# Displays.net
KiCad netlist of a schematic drawn in Altium Designer
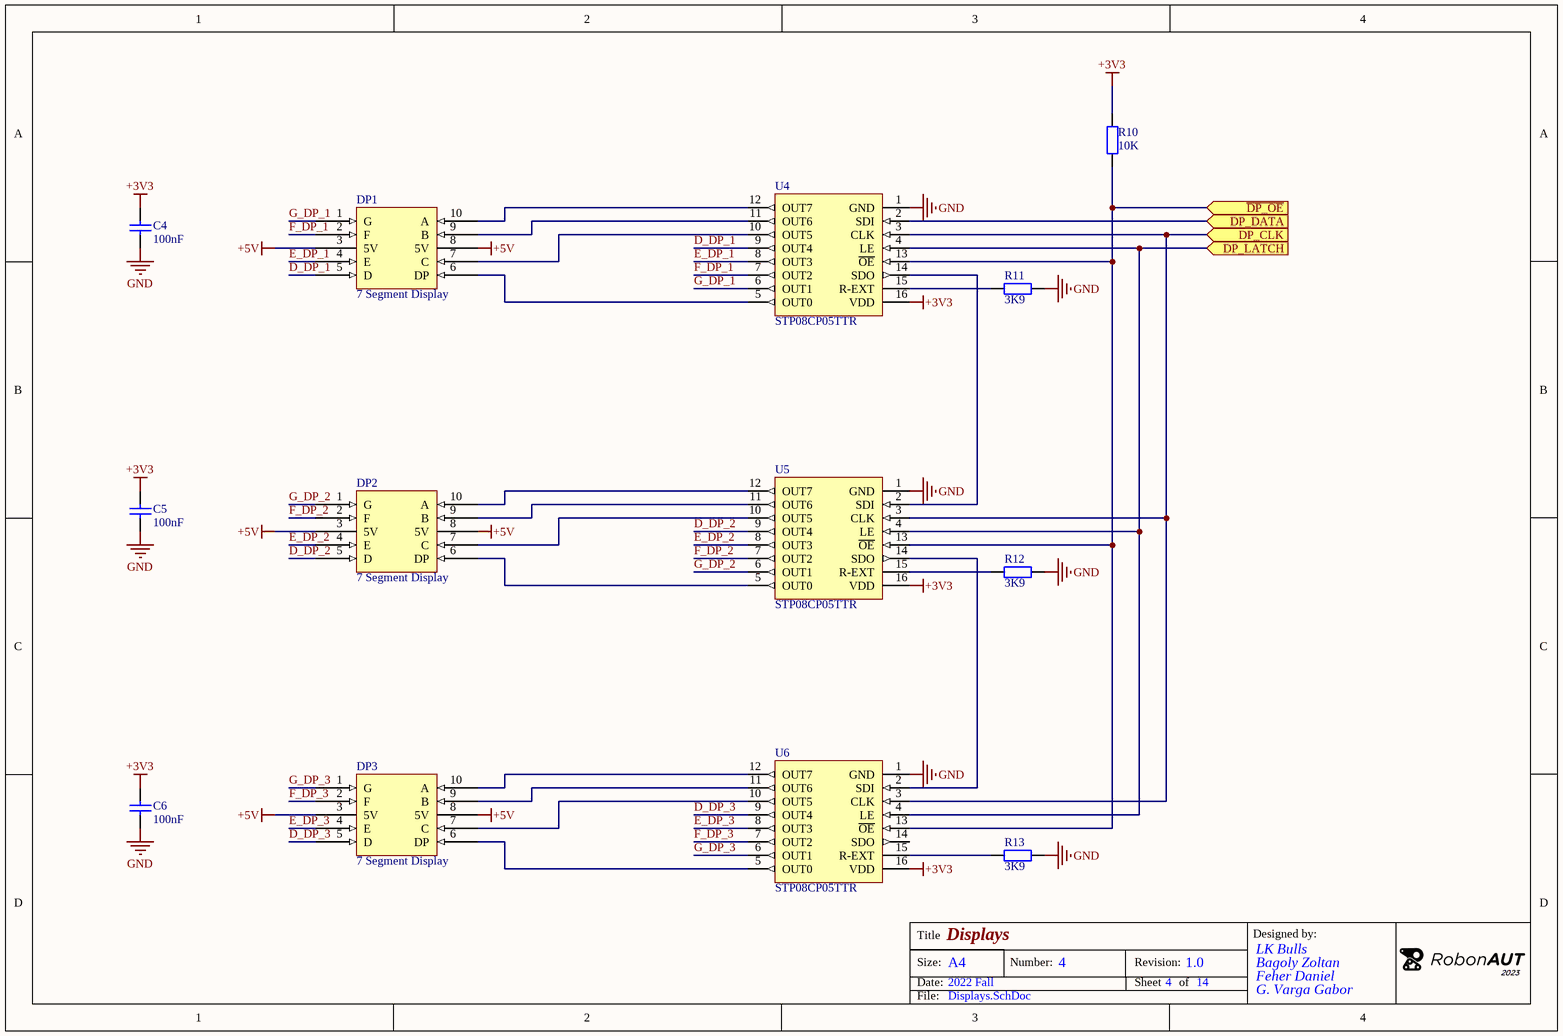
[diagram p0: Displays.SchDoc]

(export (version "E")
  (design (tool "Eeschema 10.0.6"))
  (components
    (comp (ref "C4")
      (value "100nF")
      (footprint "FP_0805_CAP_085")
      (description "Capacitor")
      (fields (field (name "TOLERANCE") "10%") (field (name "VOLTAGE") "50V"))
      (libsource (lib "LKBulls2023") (part "CAP"))
    )
    (comp (ref "C5")
      (value "100nF")
      (footprint "FP_0805_CAP_085")
      (description "Capacitor")
      (fields (field (name "TOLERANCE") "10%") (field (name "VOLTAGE") "50V"))
      (libsource (lib "LKBulls2023") (part "CAP"))
    )
    (comp (ref "C6")
      (value "100nF")
      (footprint "FP_0805_CAP_085")
      (description "Capacitor")
      (fields (field (name "TOLERANCE") "10%") (field (name "VOLTAGE") "50V"))
      (libsource (lib "LKBulls2023") (part "CAP"))
    )
    (comp (ref "DP1")
      (value "7 Segment Display")
      (footprint "FP_7_Segment_Display")
      (libsource (lib "LKBulls2023") (part "7_Segment_Display"))
    )
    (comp (ref "DP2")
      (value "7 Segment Display")
      (footprint "FP_7_Segment_Display")
      (libsource (lib "LKBulls2023") (part "7_Segment_Display"))
    )
    (comp (ref "DP3")
      (value "7 Segment Display")
      (footprint "FP_7_Segment_Display")
      (libsource (lib "LKBulls2023") (part "7_Segment_Display"))
    )
    (comp (ref "R10")
      (value "10K")
      (footprint "FP_0805_RES")
      (description "Resistor")
      (fields (field (name "TOLERANCE") "5%") (field (name "POWER") "0.125W"))
      (libsource (lib "") (part "RES_1"))
    )
    (comp (ref "R11")
      (value "3K9")
      (footprint "FP_0805_RES")
      (description "Resistor")
      (fields (field (name "TOLERANCE") "5%") (field (name "POWER") "0.125W"))
      (libsource (lib "LKBulls2023") (part "RES"))
    )
    (comp (ref "R12")
      (value "3K9")
      (footprint "FP_0805_RES")
      (description "Resistor")
      (fields (field (name "TOLERANCE") "5%") (field (name "POWER") "0.125W"))
      (libsource (lib "LKBulls2023") (part "RES"))
    )
    (comp (ref "R13")
      (value "3K9")
      (footprint "FP_0805_RES")
      (description "Resistor")
      (fields (field (name "TOLERANCE") "5%") (field (name "POWER") "0.125W"))
      (libsource (lib "LKBulls2023") (part "RES"))
    )
    (comp (ref "U4")
      (value "STP08CP05TTR")
      (footprint "SOP127P600-sajat_0095-015")
      (description "Low voltage, low current power 8-bit shift register")
      (libsource (lib "LKBulls2023") (part "STP08CP05TTR"))
    )
    (comp (ref "U5")
      (value "STP08CP05TTR")
      (footprint "SOP127P600-sajat_0095-015")
      (description "Low voltage, low current power 8-bit shift register")
      (libsource (lib "LKBulls2023") (part "STP08CP05TTR"))
    )
    (comp (ref "U6")
      (value "STP08CP05TTR")
      (footprint "SOP127P600-sajat_0095-015")
      (description "Low voltage, low current power 8-bit shift register")
      (libsource (lib "LKBulls2023") (part "STP08CP05TTR"))
    )
  )
  (nets
    (net (code "1") (name "+3V3") (class "Default")
      (node (ref "C4") (pin "2") (pinfunction "2_2") (pintype "passive"))
      (node (ref "C5") (pin "2") (pinfunction "2_2") (pintype "passive"))
      (node (ref "C6") (pin "2") (pinfunction "2_2") (pintype "passive"))
      (node (ref "R10") (pin "2") (pinfunction "2_2") (pintype "passive"))
      (node (ref "U4") (pin "16") (pinfunction "VDD_16") (pintype "power_in"))
      (node (ref "U5") (pin "16") (pinfunction "VDD_16") (pintype "power_in"))
      (node (ref "U6") (pin "16") (pinfunction "VDD_16") (pintype "power_in"))
    )
    (net (code "2") (name "+5V") (class "Default")
      (node (ref "DP1") (pin "3") (pinfunction "5V_3") (pintype "power_in"))
      (node (ref "DP1") (pin "8") (pinfunction "5V_8") (pintype "power_in"))
      (node (ref "DP2") (pin "3") (pinfunction "5V_3") (pintype "power_in"))
      (node (ref "DP2") (pin "8") (pinfunction "5V_8") (pintype "power_in"))
      (node (ref "DP3") (pin "3") (pinfunction "5V_3") (pintype "power_in"))
      (node (ref "DP3") (pin "8") (pinfunction "5V_8") (pintype "power_in"))
    )
    (net (code "3") (name "/DP_CLK") (class "Default")
      (node (ref "U4") (pin "3") (pinfunction "CLK_3") (pintype "input"))
      (node (ref "U5") (pin "3") (pinfunction "CLK_3") (pintype "input"))
      (node (ref "U6") (pin "3") (pinfunction "CLK_3") (pintype "input"))
    )
    (net (code "4") (name "/DP_DATA") (class "Default")
      (node (ref "U4") (pin "2") (pinfunction "SDI_2") (pintype "input"))
    )
    (net (code "5") (name "/DP_LATCH") (class "Default")
      (node (ref "U4") (pin "4") (pinfunction "LE_4") (pintype "input"))
      (node (ref "U5") (pin "4") (pinfunction "LE_4") (pintype "input"))
      (node (ref "U6") (pin "4") (pinfunction "LE_4") (pintype "input"))
    )
    (net (code "6") (name "/D_DP_1") (class "Default")
      (node (ref "DP1") (pin "5") (pinfunction "D_5") (pintype "input"))
      (node (ref "U4") (pin "9") (pinfunction "OUT4_9") (pintype "output"))
    )
    (net (code "7") (name "/D_DP_2") (class "Default")
      (node (ref "DP2") (pin "5") (pinfunction "D_5") (pintype "input"))
      (node (ref "U5") (pin "9") (pinfunction "OUT4_9") (pintype "output"))
    )
    (net (code "8") (name "/D_DP_3") (class "Default")
      (node (ref "DP3") (pin "5") (pinfunction "D_5") (pintype "input"))
      (node (ref "U6") (pin "9") (pinfunction "OUT4_9") (pintype "output"))
    )
    (net (code "9") (name "/E_DP_1") (class "Default")
      (node (ref "DP1") (pin "4") (pinfunction "E_4") (pintype "input"))
      (node (ref "U4") (pin "8") (pinfunction "OUT3_8") (pintype "output"))
    )
    (net (code "10") (name "/E_DP_2") (class "Default")
      (node (ref "DP2") (pin "4") (pinfunction "E_4") (pintype "input"))
      (node (ref "U5") (pin "8") (pinfunction "OUT3_8") (pintype "output"))
    )
    (net (code "11") (name "/E_DP_3") (class "Default")
      (node (ref "DP3") (pin "4") (pinfunction "E_4") (pintype "input"))
      (node (ref "U6") (pin "8") (pinfunction "OUT3_8") (pintype "output"))
    )
    (net (code "12") (name "/F_DP_1") (class "Default")
      (node (ref "DP1") (pin "2") (pinfunction "F_2") (pintype "input"))
      (node (ref "U4") (pin "7") (pinfunction "OUT2_7") (pintype "output"))
    )
    (net (code "13") (name "/F_DP_2") (class "Default")
      (node (ref "DP2") (pin "2") (pinfunction "F_2") (pintype "input"))
      (node (ref "U5") (pin "7") (pinfunction "OUT2_7") (pintype "output"))
    )
    (net (code "14") (name "/F_DP_3") (class "Default")
      (node (ref "DP3") (pin "2") (pinfunction "F_2") (pintype "input"))
      (node (ref "U6") (pin "7") (pinfunction "OUT2_7") (pintype "output"))
    )
    (net (code "15") (name "/G_DP_1") (class "Default")
      (node (ref "DP1") (pin "1") (pinfunction "G_1") (pintype "input"))
      (node (ref "U4") (pin "6") (pinfunction "OUT1_6") (pintype "output"))
    )
    (net (code "16") (name "/G_DP_2") (class "Default")
      (node (ref "DP2") (pin "1") (pinfunction "G_1") (pintype "input"))
      (node (ref "U5") (pin "6") (pinfunction "OUT1_6") (pintype "output"))
    )
    (net (code "17") (name "/G_DP_3") (class "Default")
      (node (ref "DP3") (pin "1") (pinfunction "G_1") (pintype "input"))
      (node (ref "U6") (pin "6") (pinfunction "OUT1_6") (pintype "output"))
    )
    (net (code "18") (name "/~{DP_OE}") (class "Default")
      (node (ref "R10") (pin "1") (pinfunction "1_1") (pintype "passive"))
      (node (ref "U4") (pin "13") (pinfunction "~{OE}_13") (pintype "input"))
      (node (ref "U5") (pin "13") (pinfunction "~{OE}_13") (pintype "input"))
      (node (ref "U6") (pin "13") (pinfunction "~{OE}_13") (pintype "input"))
    )
    (net (code "19") (name "GND") (class "Default")
      (node (ref "C4") (pin "1") (pinfunction "1_1") (pintype "passive"))
      (node (ref "C5") (pin "1") (pinfunction "1_1") (pintype "passive"))
      (node (ref "C6") (pin "1") (pinfunction "1_1") (pintype "passive"))
      (node (ref "R11") (pin "2") (pinfunction "2_2") (pintype "passive"))
      (node (ref "R12") (pin "2") (pinfunction "2_2") (pintype "passive"))
      (node (ref "R13") (pin "2") (pinfunction "2_2") (pintype "passive"))
      (node (ref "U4") (pin "1") (pinfunction "GND_1") (pintype "passive"))
      (node (ref "U5") (pin "1") (pinfunction "GND_1") (pintype "passive"))
      (node (ref "U6") (pin "1") (pinfunction "GND_1") (pintype "passive"))
    )
    (net (code "20") (name "Net-(DP1-A)") (class "Default")
      (node (ref "DP1") (pin "10") (pinfunction "A_10") (pintype "input"))
      (node (ref "U4") (pin "12") (pinfunction "OUT7_12") (pintype "output"))
    )
    (net (code "21") (name "Net-(DP1-B)") (class "Default")
      (node (ref "DP1") (pin "9") (pinfunction "B_9") (pintype "input"))
      (node (ref "U4") (pin "11") (pinfunction "OUT6_11") (pintype "output"))
    )
    (net (code "22") (name "Net-(DP1-C)") (class "Default")
      (node (ref "DP1") (pin "7") (pinfunction "C_7") (pintype "input"))
      (node (ref "U4") (pin "10") (pinfunction "OUT5_10") (pintype "output"))
    )
    (net (code "23") (name "Net-(DP1-DP)") (class "Default")
      (node (ref "DP1") (pin "6") (pinfunction "DP_6") (pintype "input"))
      (node (ref "U4") (pin "5") (pinfunction "OUT0_5") (pintype "output"))
    )
    (net (code "24") (name "Net-(DP2-A)") (class "Default")
      (node (ref "DP2") (pin "10") (pinfunction "A_10") (pintype "input"))
      (node (ref "U5") (pin "12") (pinfunction "OUT7_12") (pintype "output"))
    )
    (net (code "25") (name "Net-(DP2-B)") (class "Default")
      (node (ref "DP2") (pin "9") (pinfunction "B_9") (pintype "input"))
      (node (ref "U5") (pin "11") (pinfunction "OUT6_11") (pintype "output"))
    )
    (net (code "26") (name "Net-(DP2-C)") (class "Default")
      (node (ref "DP2") (pin "7") (pinfunction "C_7") (pintype "input"))
      (node (ref "U5") (pin "10") (pinfunction "OUT5_10") (pintype "output"))
    )
    (net (code "27") (name "Net-(DP2-DP)") (class "Default")
      (node (ref "DP2") (pin "6") (pinfunction "DP_6") (pintype "input"))
      (node (ref "U5") (pin "5") (pinfunction "OUT0_5") (pintype "output"))
    )
    (net (code "28") (name "Net-(DP3-A)") (class "Default")
      (node (ref "DP3") (pin "10") (pinfunction "A_10") (pintype "input"))
      (node (ref "U6") (pin "12") (pinfunction "OUT7_12") (pintype "output"))
    )
    (net (code "29") (name "Net-(DP3-B)") (class "Default")
      (node (ref "DP3") (pin "9") (pinfunction "B_9") (pintype "input"))
      (node (ref "U6") (pin "11") (pinfunction "OUT6_11") (pintype "output"))
    )
    (net (code "30") (name "Net-(DP3-C)") (class "Default")
      (node (ref "DP3") (pin "7") (pinfunction "C_7") (pintype "input"))
      (node (ref "U6") (pin "10") (pinfunction "OUT5_10") (pintype "output"))
    )
    (net (code "31") (name "Net-(DP3-DP)") (class "Default")
      (node (ref "DP3") (pin "6") (pinfunction "DP_6") (pintype "input"))
      (node (ref "U6") (pin "5") (pinfunction "OUT0_5") (pintype "output"))
    )
    (net (code "32") (name "Net-(U4-R-EXT)") (class "Default")
      (node (ref "R11") (pin "1") (pinfunction "1_1") (pintype "passive"))
      (node (ref "U4") (pin "15") (pinfunction "R-EXT_15") (pintype "passive"))
    )
    (net (code "33") (name "Net-(U4-SDO)") (class "Default")
      (node (ref "U4") (pin "14") (pinfunction "SDO_14") (pintype "output"))
      (node (ref "U5") (pin "2") (pinfunction "SDI_2") (pintype "input"))
    )
    (net (code "34") (name "Net-(U5-R-EXT)") (class "Default")
      (node (ref "R12") (pin "1") (pinfunction "1_1") (pintype "passive"))
      (node (ref "U5") (pin "15") (pinfunction "R-EXT_15") (pintype "passive"))
    )
    (net (code "35") (name "Net-(U5-SDO)") (class "Default")
      (node (ref "U5") (pin "14") (pinfunction "SDO_14") (pintype "output"))
      (node (ref "U6") (pin "2") (pinfunction "SDI_2") (pintype "input"))
    )
    (net (code "36") (name "Net-(U6-R-EXT)") (class "Default")
      (node (ref "R13") (pin "1") (pinfunction "1_1") (pintype "passive"))
      (node (ref "U6") (pin "15") (pinfunction "R-EXT_15") (pintype "passive"))
    )
    (net (code "37") (name "unconnected-(U6-SDO-Pad14)") (class "Default")
      (node (ref "U6") (pin "14") (pinfunction "SDO_14") (pintype "output"))
    )
  )
)
